# tiny_breadboard.net
KiCad netlist of a schematic drawn in EAGLE
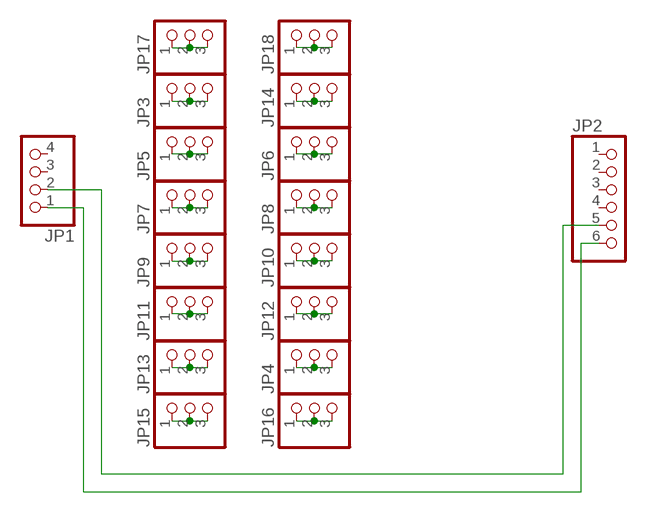
[diagram p0: schematic, sheet 1]

(export (version "E")
  (design (tool "Eeschema 10.0.6"))
  (components
    (comp (ref "JP1")
      (value "PINHD-1X4")
      (footprint "eagle-import:1X04")
      (libsource (lib "eagle-import") (part "PINHD-1X4"))
    )
    (comp (ref "JP2")
      (value "PINHD-1X6")
      (footprint "eagle-import:1X06")
      (libsource (lib "eagle-import") (part "PINHD-1X6"))
    )
    (comp (ref "JP3")
      (value "PINHD-1X3")
      (footprint "eagle-import:1X03")
      (libsource (lib "eagle-import") (part "PINHD-1X3"))
    )
    (comp (ref "JP4")
      (value "PINHD-1X3")
      (footprint "eagle-import:1X03")
      (libsource (lib "eagle-import") (part "PINHD-1X3"))
    )
    (comp (ref "JP5")
      (value "PINHD-1X3")
      (footprint "eagle-import:1X03")
      (libsource (lib "eagle-import") (part "PINHD-1X3"))
    )
    (comp (ref "JP6")
      (value "PINHD-1X3")
      (footprint "eagle-import:1X03")
      (libsource (lib "eagle-import") (part "PINHD-1X3"))
    )
    (comp (ref "JP7")
      (value "PINHD-1X3")
      (footprint "eagle-import:1X03")
      (libsource (lib "eagle-import") (part "PINHD-1X3"))
    )
    (comp (ref "JP8")
      (value "PINHD-1X3")
      (footprint "eagle-import:1X03")
      (libsource (lib "eagle-import") (part "PINHD-1X3"))
    )
    (comp (ref "JP9")
      (value "PINHD-1X3")
      (footprint "eagle-import:1X03")
      (libsource (lib "eagle-import") (part "PINHD-1X3"))
    )
    (comp (ref "JP10")
      (value "PINHD-1X3")
      (footprint "eagle-import:1X03")
      (libsource (lib "eagle-import") (part "PINHD-1X3"))
    )
    (comp (ref "JP11")
      (value "PINHD-1X3")
      (footprint "eagle-import:1X03")
      (libsource (lib "eagle-import") (part "PINHD-1X3"))
    )
    (comp (ref "JP12")
      (value "PINHD-1X3")
      (footprint "eagle-import:1X03")
      (libsource (lib "eagle-import") (part "PINHD-1X3"))
    )
    (comp (ref "JP13")
      (value "PINHD-1X3")
      (footprint "eagle-import:1X03")
      (libsource (lib "eagle-import") (part "PINHD-1X3"))
    )
    (comp (ref "JP14")
      (value "PINHD-1X3")
      (footprint "eagle-import:1X03")
      (libsource (lib "eagle-import") (part "PINHD-1X3"))
    )
    (comp (ref "JP15")
      (value "PINHD-1X3")
      (footprint "eagle-import:1X03")
      (libsource (lib "eagle-import") (part "PINHD-1X3"))
    )
    (comp (ref "JP16")
      (value "PINHD-1X3")
      (footprint "eagle-import:1X03")
      (libsource (lib "eagle-import") (part "PINHD-1X3"))
    )
    (comp (ref "JP17")
      (value "PINHD-1X3")
      (footprint "eagle-import:1X03")
      (libsource (lib "eagle-import") (part "PINHD-1X3"))
    )
    (comp (ref "JP18")
      (value "PINHD-1X3")
      (footprint "eagle-import:1X03")
      (libsource (lib "eagle-import") (part "PINHD-1X3"))
    )
  )
  (nets
    (net (code "1") (name "Net-(JP1-Pad1)") (class "Default")
      (node (ref "JP1") (pin "1") (pinfunction "1_1") (pintype "passive"))
      (node (ref "JP2") (pin "6") (pinfunction "6_6") (pintype "passive"))
    )
    (net (code "2") (name "Net-(JP1-Pad2)") (class "Default")
      (node (ref "JP1") (pin "2") (pinfunction "2_2") (pintype "passive"))
      (node (ref "JP2") (pin "5") (pinfunction "5_5") (pintype "passive"))
    )
    (net (code "3") (name "Net-(JP3-Pad1)") (class "Default")
      (node (ref "JP3") (pin "1") (pinfunction "1_1") (pintype "passive"))
      (node (ref "JP3") (pin "2") (pinfunction "2_2") (pintype "passive"))
      (node (ref "JP3") (pin "3") (pinfunction "3_3") (pintype "passive"))
    )
    (net (code "4") (name "Net-(JP4-Pad1)") (class "Default")
      (node (ref "JP4") (pin "1") (pinfunction "1_1") (pintype "passive"))
      (node (ref "JP4") (pin "2") (pinfunction "2_2") (pintype "passive"))
      (node (ref "JP4") (pin "3") (pinfunction "3_3") (pintype "passive"))
    )
    (net (code "5") (name "Net-(JP5-Pad1)") (class "Default")
      (node (ref "JP5") (pin "1") (pinfunction "1_1") (pintype "passive"))
      (node (ref "JP5") (pin "2") (pinfunction "2_2") (pintype "passive"))
      (node (ref "JP5") (pin "3") (pinfunction "3_3") (pintype "passive"))
    )
    (net (code "6") (name "Net-(JP6-Pad1)") (class "Default")
      (node (ref "JP6") (pin "1") (pinfunction "1_1") (pintype "passive"))
      (node (ref "JP6") (pin "2") (pinfunction "2_2") (pintype "passive"))
      (node (ref "JP6") (pin "3") (pinfunction "3_3") (pintype "passive"))
    )
    (net (code "7") (name "Net-(JP7-Pad1)") (class "Default")
      (node (ref "JP7") (pin "1") (pinfunction "1_1") (pintype "passive"))
      (node (ref "JP7") (pin "2") (pinfunction "2_2") (pintype "passive"))
      (node (ref "JP7") (pin "3") (pinfunction "3_3") (pintype "passive"))
    )
    (net (code "8") (name "Net-(JP8-Pad1)") (class "Default")
      (node (ref "JP8") (pin "1") (pinfunction "1_1") (pintype "passive"))
      (node (ref "JP8") (pin "2") (pinfunction "2_2") (pintype "passive"))
      (node (ref "JP8") (pin "3") (pinfunction "3_3") (pintype "passive"))
    )
    (net (code "9") (name "Net-(JP9-Pad1)") (class "Default")
      (node (ref "JP9") (pin "1") (pinfunction "1_1") (pintype "passive"))
      (node (ref "JP9") (pin "2") (pinfunction "2_2") (pintype "passive"))
      (node (ref "JP9") (pin "3") (pinfunction "3_3") (pintype "passive"))
    )
    (net (code "10") (name "Net-(JP10-Pad1)") (class "Default")
      (node (ref "JP10") (pin "1") (pinfunction "1_1") (pintype "passive"))
      (node (ref "JP10") (pin "2") (pinfunction "2_2") (pintype "passive"))
      (node (ref "JP10") (pin "3") (pinfunction "3_3") (pintype "passive"))
    )
    (net (code "11") (name "Net-(JP11-Pad1)") (class "Default")
      (node (ref "JP11") (pin "1") (pinfunction "1_1") (pintype "passive"))
      (node (ref "JP11") (pin "2") (pinfunction "2_2") (pintype "passive"))
      (node (ref "JP11") (pin "3") (pinfunction "3_3") (pintype "passive"))
    )
    (net (code "12") (name "Net-(JP12-Pad1)") (class "Default")
      (node (ref "JP12") (pin "1") (pinfunction "1_1") (pintype "passive"))
      (node (ref "JP12") (pin "2") (pinfunction "2_2") (pintype "passive"))
      (node (ref "JP12") (pin "3") (pinfunction "3_3") (pintype "passive"))
    )
    (net (code "13") (name "Net-(JP13-Pad1)") (class "Default")
      (node (ref "JP13") (pin "1") (pinfunction "1_1") (pintype "passive"))
      (node (ref "JP13") (pin "2") (pinfunction "2_2") (pintype "passive"))
      (node (ref "JP13") (pin "3") (pinfunction "3_3") (pintype "passive"))
    )
    (net (code "14") (name "Net-(JP14-Pad1)") (class "Default")
      (node (ref "JP14") (pin "1") (pinfunction "1_1") (pintype "passive"))
      (node (ref "JP14") (pin "2") (pinfunction "2_2") (pintype "passive"))
      (node (ref "JP14") (pin "3") (pinfunction "3_3") (pintype "passive"))
    )
    (net (code "15") (name "Net-(JP15-Pad1)") (class "Default")
      (node (ref "JP15") (pin "1") (pinfunction "1_1") (pintype "passive"))
      (node (ref "JP15") (pin "2") (pinfunction "2_2") (pintype "passive"))
      (node (ref "JP15") (pin "3") (pinfunction "3_3") (pintype "passive"))
    )
    (net (code "16") (name "Net-(JP16-Pad1)") (class "Default")
      (node (ref "JP16") (pin "1") (pinfunction "1_1") (pintype "passive"))
      (node (ref "JP16") (pin "2") (pinfunction "2_2") (pintype "passive"))
      (node (ref "JP16") (pin "3") (pinfunction "3_3") (pintype "passive"))
    )
    (net (code "17") (name "Net-(JP17-Pad1)") (class "Default")
      (node (ref "JP17") (pin "1") (pinfunction "1_1") (pintype "passive"))
      (node (ref "JP17") (pin "2") (pinfunction "2_2") (pintype "passive"))
      (node (ref "JP17") (pin "3") (pinfunction "3_3") (pintype "passive"))
    )
    (net (code "18") (name "Net-(JP18-Pad1)") (class "Default")
      (node (ref "JP18") (pin "1") (pinfunction "1_1") (pintype "passive"))
      (node (ref "JP18") (pin "2") (pinfunction "2_2") (pintype "passive"))
      (node (ref "JP18") (pin "3") (pinfunction "3_3") (pintype "passive"))
    )
    (net (code "19") (name "unconnected-(JP1-Pad3)") (class "Default")
      (node (ref "JP1") (pin "3") (pinfunction "3_3") (pintype "passive"))
    )
    (net (code "20") (name "unconnected-(JP1-Pad4)") (class "Default")
      (node (ref "JP1") (pin "4") (pinfunction "4_4") (pintype "passive"))
    )
    (net (code "21") (name "unconnected-(JP2-Pad1)") (class "Default")
      (node (ref "JP2") (pin "1") (pinfunction "1_1") (pintype "passive"))
    )
    (net (code "22") (name "unconnected-(JP2-Pad2)") (class "Default")
      (node (ref "JP2") (pin "2") (pinfunction "2_2") (pintype "passive"))
    )
    (net (code "23") (name "unconnected-(JP2-Pad3)") (class "Default")
      (node (ref "JP2") (pin "3") (pinfunction "3_3") (pintype "passive"))
    )
    (net (code "24") (name "unconnected-(JP2-Pad4)") (class "Default")
      (node (ref "JP2") (pin "4") (pinfunction "4_4") (pintype "passive"))
    )
  )
)
